# calculator7.net
KiCad netlist of a schematic drawn in EAGLE
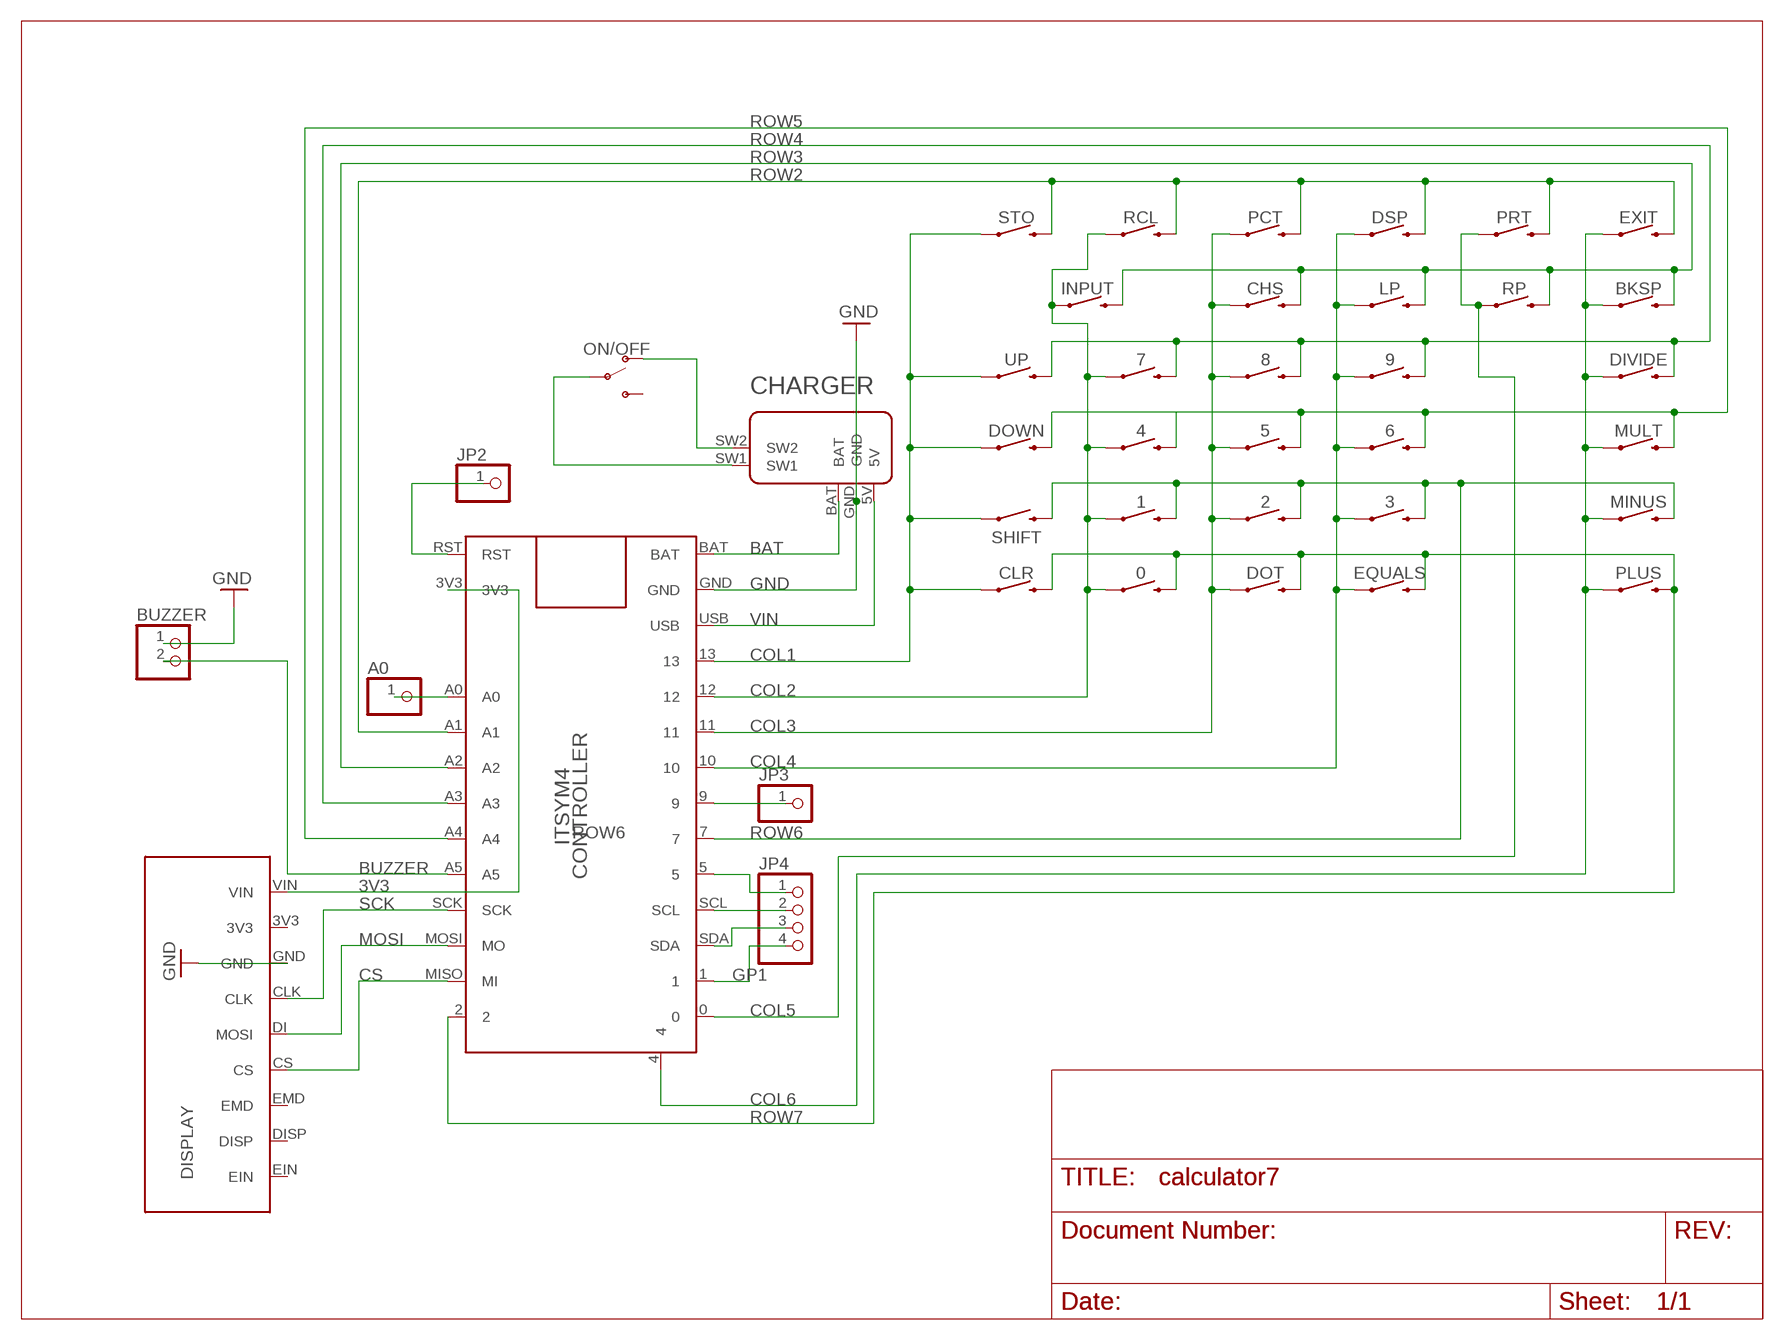
[diagram p0: schematic, sheet 1]

(export (version "E")
  (design (tool "Eeschema 10.0.6"))
  (components
    (comp (ref "0")
      (value "3BUTTON")
      (footprint "eagle-import:3BUTTON")
      (libsource (lib "eagle-import") (part "3BUTTON"))
    )
    (comp (ref "1")
      (value "3BUTTON")
      (footprint "eagle-import:3BUTTON")
      (libsource (lib "eagle-import") (part "3BUTTON"))
    )
    (comp (ref "2")
      (value "3BUTTON")
      (footprint "eagle-import:3BUTTON")
      (libsource (lib "eagle-import") (part "3BUTTON"))
    )
    (comp (ref "3")
      (value "3BUTTON")
      (footprint "eagle-import:3BUTTON")
      (libsource (lib "eagle-import") (part "3BUTTON"))
    )
    (comp (ref "4")
      (value "3BUTTON")
      (footprint "eagle-import:3BUTTON")
      (libsource (lib "eagle-import") (part "3BUTTON"))
    )
    (comp (ref "5")
      (value "3BUTTON")
      (footprint "eagle-import:3BUTTON")
      (libsource (lib "eagle-import") (part "3BUTTON"))
    )
    (comp (ref "6")
      (value "3BUTTON")
      (footprint "eagle-import:3BUTTON")
      (libsource (lib "eagle-import") (part "3BUTTON"))
    )
    (comp (ref "7")
      (value "3BUTTON")
      (footprint "eagle-import:3BUTTON")
      (libsource (lib "eagle-import") (part "3BUTTON"))
    )
    (comp (ref "8")
      (value "3BUTTON")
      (footprint "eagle-import:3BUTTON")
      (libsource (lib "eagle-import") (part "3BUTTON"))
    )
    (comp (ref "9")
      (value "3BUTTON")
      (footprint "eagle-import:3BUTTON")
      (libsource (lib "eagle-import") (part "3BUTTON"))
    )
    (comp (ref "A0")
      (value "PINHD-1X1")
      (footprint "eagle-import:1X01")
      (libsource (lib "eagle-import") (part "PINHD-1X1"))
    )
    (comp (ref "BKSP")
      (value "3BUTTON")
      (footprint "eagle-import:3BUTTON")
      (libsource (lib "eagle-import") (part "3BUTTON"))
    )
    (comp (ref "BUZZER")
      (value "PINHD-1X2")
      (footprint "eagle-import:1X02")
      (libsource (lib "eagle-import") (part "PINHD-1X2"))
    )
    (comp (ref "CHARGER")
      (value "LIPO_BACKPACK")
      (footprint "eagle-import:LIPO_BACKPACK")
      (libsource (lib "eagle-import") (part "LIPO_BACKPACK"))
    )
    (comp (ref "CHS")
      (value "3BUTTON")
      (footprint "eagle-import:3BUTTON")
      (libsource (lib "eagle-import") (part "3BUTTON"))
    )
    (comp (ref "CLR")
      (value "3BUTTON")
      (footprint "eagle-import:3BUTTON")
      (libsource (lib "eagle-import") (part "3BUTTON"))
    )
    (comp (ref "CONTROLLER")
      (value "ITSYM4")
      (footprint "eagle-import:ITSYM4")
      (libsource (lib "eagle-import") (part "ITSYM4"))
    )
    (comp (ref "DISPLAY")
      (value "SHARPMEM_FULL")
      (footprint "eagle-import:SHARPMEM_FULL")
      (libsource (lib "eagle-import") (part "SHARPMEM_FULL"))
    )
    (comp (ref "DIVIDE")
      (value "3BUTTON")
      (footprint "eagle-import:3BUTTON")
      (libsource (lib "eagle-import") (part "3BUTTON"))
    )
    (comp (ref "DOT")
      (value "3BUTTON")
      (footprint "eagle-import:3BUTTON")
      (libsource (lib "eagle-import") (part "3BUTTON"))
    )
    (comp (ref "DOWN")
      (value "3BUTTON")
      (footprint "eagle-import:3BUTTON")
      (libsource (lib "eagle-import") (part "3BUTTON"))
    )
    (comp (ref "DSP")
      (value "3BUTTON")
      (footprint "eagle-import:3BUTTON")
      (libsource (lib "eagle-import") (part "3BUTTON"))
    )
    (comp (ref "EQUALS")
      (value "3BUTTON")
      (footprint "eagle-import:3BUTTON")
      (libsource (lib "eagle-import") (part "3BUTTON"))
    )
    (comp (ref "EXIT")
      (value "3BUTTON")
      (footprint "eagle-import:3BUTTON")
      (libsource (lib "eagle-import") (part "3BUTTON"))
    )
    (comp (ref "INPUT")
      (value "3BUTTON")
      (footprint "eagle-import:3BUTTON")
      (libsource (lib "eagle-import") (part "3BUTTON"))
    )
    (comp (ref "JP2")
      (value "PINHD-1X1")
      (footprint "eagle-import:1X01")
      (libsource (lib "eagle-import") (part "PINHD-1X1"))
    )
    (comp (ref "JP3")
      (value "PINHD-1X1")
      (footprint "eagle-import:1X01")
      (libsource (lib "eagle-import") (part "PINHD-1X1"))
    )
    (comp (ref "JP4")
      (value "PINHD-1X4")
      (footprint "eagle-import:1X04")
      (libsource (lib "eagle-import") (part "PINHD-1X4"))
    )
    (comp (ref "LP")
      (value "3BUTTON")
      (footprint "eagle-import:3BUTTON")
      (libsource (lib "eagle-import") (part "3BUTTON"))
    )
    (comp (ref "MINUS")
      (value "3BUTTON")
      (footprint "eagle-import:3BUTTON")
      (libsource (lib "eagle-import") (part "3BUTTON"))
    )
    (comp (ref "MULT")
      (value "3BUTTON")
      (footprint "eagle-import:3BUTTON")
      (libsource (lib "eagle-import") (part "3BUTTON"))
    )
    (comp (ref "ON/OFF")
      (value "LIL_SWITCH")
      (footprint "eagle-import:LIL_SWITCH")
      (libsource (lib "eagle-import") (part "LIL_SWITCH"))
    )
    (comp (ref "PCT")
      (value "3BUTTON")
      (footprint "eagle-import:3BUTTON")
      (libsource (lib "eagle-import") (part "3BUTTON"))
    )
    (comp (ref "PLUS")
      (value "3BUTTON")
      (footprint "eagle-import:3BUTTON")
      (libsource (lib "eagle-import") (part "3BUTTON"))
    )
    (comp (ref "PRT")
      (value "3BUTTON")
      (footprint "eagle-import:3BUTTON")
      (libsource (lib "eagle-import") (part "3BUTTON"))
    )
    (comp (ref "RCL")
      (value "3BUTTON")
      (footprint "eagle-import:3BUTTON")
      (libsource (lib "eagle-import") (part "3BUTTON"))
    )
    (comp (ref "RP")
      (value "3BUTTON")
      (footprint "eagle-import:3BUTTON")
      (libsource (lib "eagle-import") (part "3BUTTON"))
    )
    (comp (ref "SHIFT")
      (value "3BUTTON")
      (footprint "eagle-import:3BUTTON")
      (libsource (lib "eagle-import") (part "3BUTTON"))
    )
    (comp (ref "STO")
      (value "3BUTTON")
      (footprint "eagle-import:3BUTTON")
      (libsource (lib "eagle-import") (part "3BUTTON"))
    )
    (comp (ref "UP")
      (value "3BUTTON")
      (footprint "eagle-import:3BUTTON")
      (libsource (lib "eagle-import") (part "3BUTTON"))
    )
  )
  (nets
    (net (code "1") (name "/3V3") (class "Default")
      (node (ref "CONTROLLER") (pin "3V3") (pinfunction "3V3_3V3") (pintype "bidirectional"))
      (node (ref "DISPLAY") (pin "VIN") (pinfunction "VIN_VIN") (pintype "bidirectional"))
    )
    (net (code "2") (name "/BAT") (class "Default")
      (node (ref "CHARGER") (pin "BAT") (pinfunction "BAT_BAT") (pintype "bidirectional"))
      (node (ref "CONTROLLER") (pin "BAT") (pinfunction "BAT_BAT") (pintype "bidirectional"))
    )
    (net (code "3") (name "/BUZZER") (class "Default")
      (node (ref "BUZZER") (pin "2") (pinfunction "2_2") (pintype "passive"))
      (node (ref "CONTROLLER") (pin "A5") (pinfunction "A5_A5") (pintype "bidirectional"))
    )
    (net (code "4") (name "/COL1") (class "Default")
      (node (ref "CLR") (pin "P1") (pinfunction "1_P1") (pintype "passive"))
      (node (ref "CONTROLLER") (pin "13") (pinfunction "13_13") (pintype "bidirectional"))
      (node (ref "DOWN") (pin "P1") (pinfunction "1_P1") (pintype "passive"))
      (node (ref "SHIFT") (pin "P1") (pinfunction "1_P1") (pintype "passive"))
      (node (ref "STO") (pin "P1") (pinfunction "1_P1") (pintype "passive"))
      (node (ref "UP") (pin "P1") (pinfunction "1_P1") (pintype "passive"))
    )
    (net (code "5") (name "/COL2") (class "Default")
      (node (ref "0") (pin "P1") (pinfunction "1_P1") (pintype "passive"))
      (node (ref "1") (pin "P1") (pinfunction "1_P1") (pintype "passive"))
      (node (ref "4") (pin "P1") (pinfunction "1_P1") (pintype "passive"))
      (node (ref "7") (pin "P1") (pinfunction "1_P1") (pintype "passive"))
      (node (ref "CONTROLLER") (pin "12") (pinfunction "12_12") (pintype "bidirectional"))
      (node (ref "INPUT") (pin "P1") (pinfunction "1_P1") (pintype "passive"))
      (node (ref "RCL") (pin "P1") (pinfunction "1_P1") (pintype "passive"))
    )
    (net (code "6") (name "/COL3") (class "Default")
      (node (ref "2") (pin "P1") (pinfunction "1_P1") (pintype "passive"))
      (node (ref "5") (pin "P1") (pinfunction "1_P1") (pintype "passive"))
      (node (ref "8") (pin "P1") (pinfunction "1_P1") (pintype "passive"))
      (node (ref "CHS") (pin "P1") (pinfunction "1_P1") (pintype "passive"))
      (node (ref "CONTROLLER") (pin "11") (pinfunction "11_11") (pintype "bidirectional"))
      (node (ref "DOT") (pin "P1") (pinfunction "1_P1") (pintype "passive"))
      (node (ref "PCT") (pin "P1") (pinfunction "1_P1") (pintype "passive"))
    )
    (net (code "7") (name "/COL4") (class "Default")
      (node (ref "3") (pin "P1") (pinfunction "1_P1") (pintype "passive"))
      (node (ref "6") (pin "P1") (pinfunction "1_P1") (pintype "passive"))
      (node (ref "9") (pin "P1") (pinfunction "1_P1") (pintype "passive"))
      (node (ref "CONTROLLER") (pin "10") (pinfunction "10_10") (pintype "bidirectional"))
      (node (ref "DSP") (pin "P1") (pinfunction "1_P1") (pintype "passive"))
      (node (ref "EQUALS") (pin "P1") (pinfunction "1_P1") (pintype "passive"))
      (node (ref "LP") (pin "P1") (pinfunction "1_P1") (pintype "passive"))
    )
    (net (code "8") (name "/COL5") (class "Default")
      (node (ref "CONTROLLER") (pin "0") (pinfunction "0_0") (pintype "bidirectional"))
      (node (ref "PRT") (pin "P1") (pinfunction "1_P1") (pintype "passive"))
      (node (ref "RP") (pin "P1") (pinfunction "1_P1") (pintype "passive"))
    )
    (net (code "9") (name "/COL6") (class "Default")
      (node (ref "BKSP") (pin "P1") (pinfunction "1_P1") (pintype "passive"))
      (node (ref "CONTROLLER") (pin "4") (pinfunction "4_4") (pintype "bidirectional"))
      (node (ref "DIVIDE") (pin "P1") (pinfunction "1_P1") (pintype "passive"))
      (node (ref "EXIT") (pin "P1") (pinfunction "1_P1") (pintype "passive"))
      (node (ref "MINUS") (pin "P1") (pinfunction "1_P1") (pintype "passive"))
      (node (ref "MULT") (pin "P1") (pinfunction "1_P1") (pintype "passive"))
      (node (ref "PLUS") (pin "P1") (pinfunction "1_P1") (pintype "passive"))
    )
    (net (code "10") (name "/CS") (class "Default")
      (node (ref "CONTROLLER") (pin "MISO") (pinfunction "MI_MISO") (pintype "bidirectional"))
      (node (ref "DISPLAY") (pin "CS") (pinfunction "CS_CS") (pintype "bidirectional"))
    )
    (net (code "11") (name "/GP1") (class "Default")
      (node (ref "CONTROLLER") (pin "1") (pinfunction "1_1") (pintype "bidirectional"))
      (node (ref "JP4") (pin "4") (pinfunction "4_4") (pintype "passive"))
    )
    (net (code "12") (name "/MOSI") (class "Default")
      (node (ref "CONTROLLER") (pin "MOSI") (pinfunction "MO_MOSI") (pintype "bidirectional"))
      (node (ref "DISPLAY") (pin "DI") (pinfunction "MOSI_DI") (pintype "bidirectional"))
    )
    (net (code "13") (name "/ROW2") (class "Default")
      (node (ref "CONTROLLER") (pin "A1") (pinfunction "A1_A1") (pintype "bidirectional"))
      (node (ref "DSP") (pin "P2") (pinfunction "2_P2") (pintype "passive"))
      (node (ref "EXIT") (pin "P2") (pinfunction "2_P2") (pintype "passive"))
      (node (ref "PCT") (pin "P2") (pinfunction "2_P2") (pintype "passive"))
      (node (ref "PRT") (pin "P2") (pinfunction "2_P2") (pintype "passive"))
      (node (ref "RCL") (pin "P2") (pinfunction "2_P2") (pintype "passive"))
      (node (ref "STO") (pin "P2") (pinfunction "2_P2") (pintype "passive"))
    )
    (net (code "14") (name "/ROW3") (class "Default")
      (node (ref "BKSP") (pin "P2") (pinfunction "2_P2") (pintype "passive"))
      (node (ref "CHS") (pin "P2") (pinfunction "2_P2") (pintype "passive"))
      (node (ref "CONTROLLER") (pin "A2") (pinfunction "A2_A2") (pintype "bidirectional"))
      (node (ref "INPUT") (pin "P2") (pinfunction "2_P2") (pintype "passive"))
      (node (ref "LP") (pin "P2") (pinfunction "2_P2") (pintype "passive"))
      (node (ref "RP") (pin "P2") (pinfunction "2_P2") (pintype "passive"))
    )
    (net (code "15") (name "/ROW4") (class "Default")
      (node (ref "7") (pin "P2") (pinfunction "2_P2") (pintype "passive"))
      (node (ref "8") (pin "P2") (pinfunction "2_P2") (pintype "passive"))
      (node (ref "9") (pin "P2") (pinfunction "2_P2") (pintype "passive"))
      (node (ref "CONTROLLER") (pin "A3") (pinfunction "A3_A3") (pintype "bidirectional"))
      (node (ref "DIVIDE") (pin "P2") (pinfunction "2_P2") (pintype "passive"))
      (node (ref "UP") (pin "P2") (pinfunction "2_P2") (pintype "passive"))
    )
    (net (code "16") (name "/ROW5") (class "Default")
      (node (ref "4") (pin "P2") (pinfunction "2_P2") (pintype "passive"))
      (node (ref "5") (pin "P2") (pinfunction "2_P2") (pintype "passive"))
      (node (ref "6") (pin "P2") (pinfunction "2_P2") (pintype "passive"))
      (node (ref "CONTROLLER") (pin "A4") (pinfunction "A4_A4") (pintype "bidirectional"))
      (node (ref "DOWN") (pin "P2") (pinfunction "2_P2") (pintype "passive"))
      (node (ref "MULT") (pin "P2") (pinfunction "2_P2") (pintype "passive"))
    )
    (net (code "17") (name "/ROW6") (class "Default")
      (node (ref "1") (pin "P2") (pinfunction "2_P2") (pintype "passive"))
      (node (ref "2") (pin "P2") (pinfunction "2_P2") (pintype "passive"))
      (node (ref "3") (pin "P2") (pinfunction "2_P2") (pintype "passive"))
      (node (ref "CONTROLLER") (pin "7") (pinfunction "7_7") (pintype "bidirectional"))
      (node (ref "MINUS") (pin "P2") (pinfunction "2_P2") (pintype "passive"))
      (node (ref "SHIFT") (pin "P2") (pinfunction "2_P2") (pintype "passive"))
    )
    (net (code "18") (name "/ROW7") (class "Default")
      (node (ref "0") (pin "P2") (pinfunction "2_P2") (pintype "passive"))
      (node (ref "CLR") (pin "P2") (pinfunction "2_P2") (pintype "passive"))
      (node (ref "CONTROLLER") (pin "2") (pinfunction "2_2") (pintype "bidirectional"))
      (node (ref "DOT") (pin "P2") (pinfunction "2_P2") (pintype "passive"))
      (node (ref "EQUALS") (pin "P2") (pinfunction "2_P2") (pintype "passive"))
      (node (ref "PLUS") (pin "P2") (pinfunction "2_P2") (pintype "passive"))
    )
    (net (code "19") (name "/SCK") (class "Default")
      (node (ref "CONTROLLER") (pin "SCK") (pinfunction "SCK_SCK") (pintype "bidirectional"))
      (node (ref "DISPLAY") (pin "CLK") (pinfunction "CLK_CLK") (pintype "bidirectional"))
    )
    (net (code "20") (name "/VIN") (class "Default")
      (node (ref "CHARGER") (pin "5V") (pinfunction "5V_5V") (pintype "bidirectional"))
      (node (ref "CONTROLLER") (pin "USB") (pinfunction "USB_USB") (pintype "bidirectional"))
    )
    (net (code "21") (name "GND") (class "Default")
      (node (ref "BUZZER") (pin "1") (pinfunction "1_1") (pintype "passive"))
      (node (ref "CHARGER") (pin "GND") (pinfunction "GND_GND") (pintype "bidirectional"))
      (node (ref "CONTROLLER") (pin "GND") (pinfunction "GND_GND") (pintype "bidirectional"))
      (node (ref "DISPLAY") (pin "GND") (pinfunction "GND_GND") (pintype "bidirectional"))
    )
    (net (code "22") (name "Net-(A0-Pad1)") (class "Default")
      (node (ref "A0") (pin "1") (pinfunction "1_1") (pintype "passive"))
      (node (ref "CONTROLLER") (pin "A0") (pinfunction "A0_A0") (pintype "bidirectional"))
    )
    (net (code "23") (name "Net-(CHARGER-PadSW1)") (class "Default")
      (node (ref "CHARGER") (pin "SW1") (pinfunction "SW1_SW1") (pintype "bidirectional"))
      (node (ref "ON/OFF") (pin "COM") (pinfunction "COM_COM") (pintype "passive"))
    )
    (net (code "24") (name "Net-(CHARGER-PadSW2)") (class "Default")
      (node (ref "CHARGER") (pin "SW2") (pinfunction "SW2_SW2") (pintype "bidirectional"))
      (node (ref "ON/OFF") (pin "P1") (pinfunction "P1_P1") (pintype "passive"))
    )
    (net (code "25") (name "Net-(CONTROLLER-Pad5)") (class "Default")
      (node (ref "CONTROLLER") (pin "5") (pinfunction "5_5") (pintype "bidirectional"))
      (node (ref "JP4") (pin "1") (pinfunction "1_1") (pintype "passive"))
    )
    (net (code "26") (name "Net-(CONTROLLER-Pad9)") (class "Default")
      (node (ref "CONTROLLER") (pin "9") (pinfunction "9_9") (pintype "bidirectional"))
      (node (ref "JP3") (pin "1") (pinfunction "1_1") (pintype "passive"))
    )
    (net (code "27") (name "Net-(CONTROLLER-PadRST)") (class "Default")
      (node (ref "CONTROLLER") (pin "RST") (pinfunction "RST_RST") (pintype "bidirectional"))
      (node (ref "JP2") (pin "1") (pinfunction "1_1") (pintype "passive"))
    )
    (net (code "28") (name "Net-(CONTROLLER-PadSCL)") (class "Default")
      (node (ref "CONTROLLER") (pin "SCL") (pinfunction "SCL_SCL") (pintype "bidirectional"))
      (node (ref "JP4") (pin "2") (pinfunction "2_2") (pintype "passive"))
    )
    (net (code "29") (name "Net-(CONTROLLER-PadSDA)") (class "Default")
      (node (ref "CONTROLLER") (pin "SDA") (pinfunction "SDA_SDA") (pintype "bidirectional"))
      (node (ref "JP4") (pin "3") (pinfunction "3_3") (pintype "passive"))
    )
    (net (code "30") (name "unconnected-(DISPLAY-Pad3V3)") (class "Default")
      (node (ref "DISPLAY") (pin "3V3") (pinfunction "3V3_3V3") (pintype "bidirectional"))
    )
    (net (code "31") (name "unconnected-(DISPLAY-PadDISP)") (class "Default")
      (node (ref "DISPLAY") (pin "DISP") (pinfunction "DISP_DISP") (pintype "bidirectional"))
    )
    (net (code "32") (name "unconnected-(DISPLAY-PadEIN)") (class "Default")
      (node (ref "DISPLAY") (pin "EIN") (pinfunction "EIN_EIN") (pintype "bidirectional"))
    )
    (net (code "33") (name "unconnected-(DISPLAY-PadEMD)") (class "Default")
      (node (ref "DISPLAY") (pin "EMD") (pinfunction "EMD_EMD") (pintype "bidirectional"))
    )
    (net (code "34") (name "unconnected-(ON/OFF-PadP2)") (class "Default")
      (node (ref "ON/OFF") (pin "P2") (pinfunction "P2_P2") (pintype "passive"))
    )
  )
)
